# power-systems-v3.net
KiCad netlist of a schematic drawn in Altium Designer
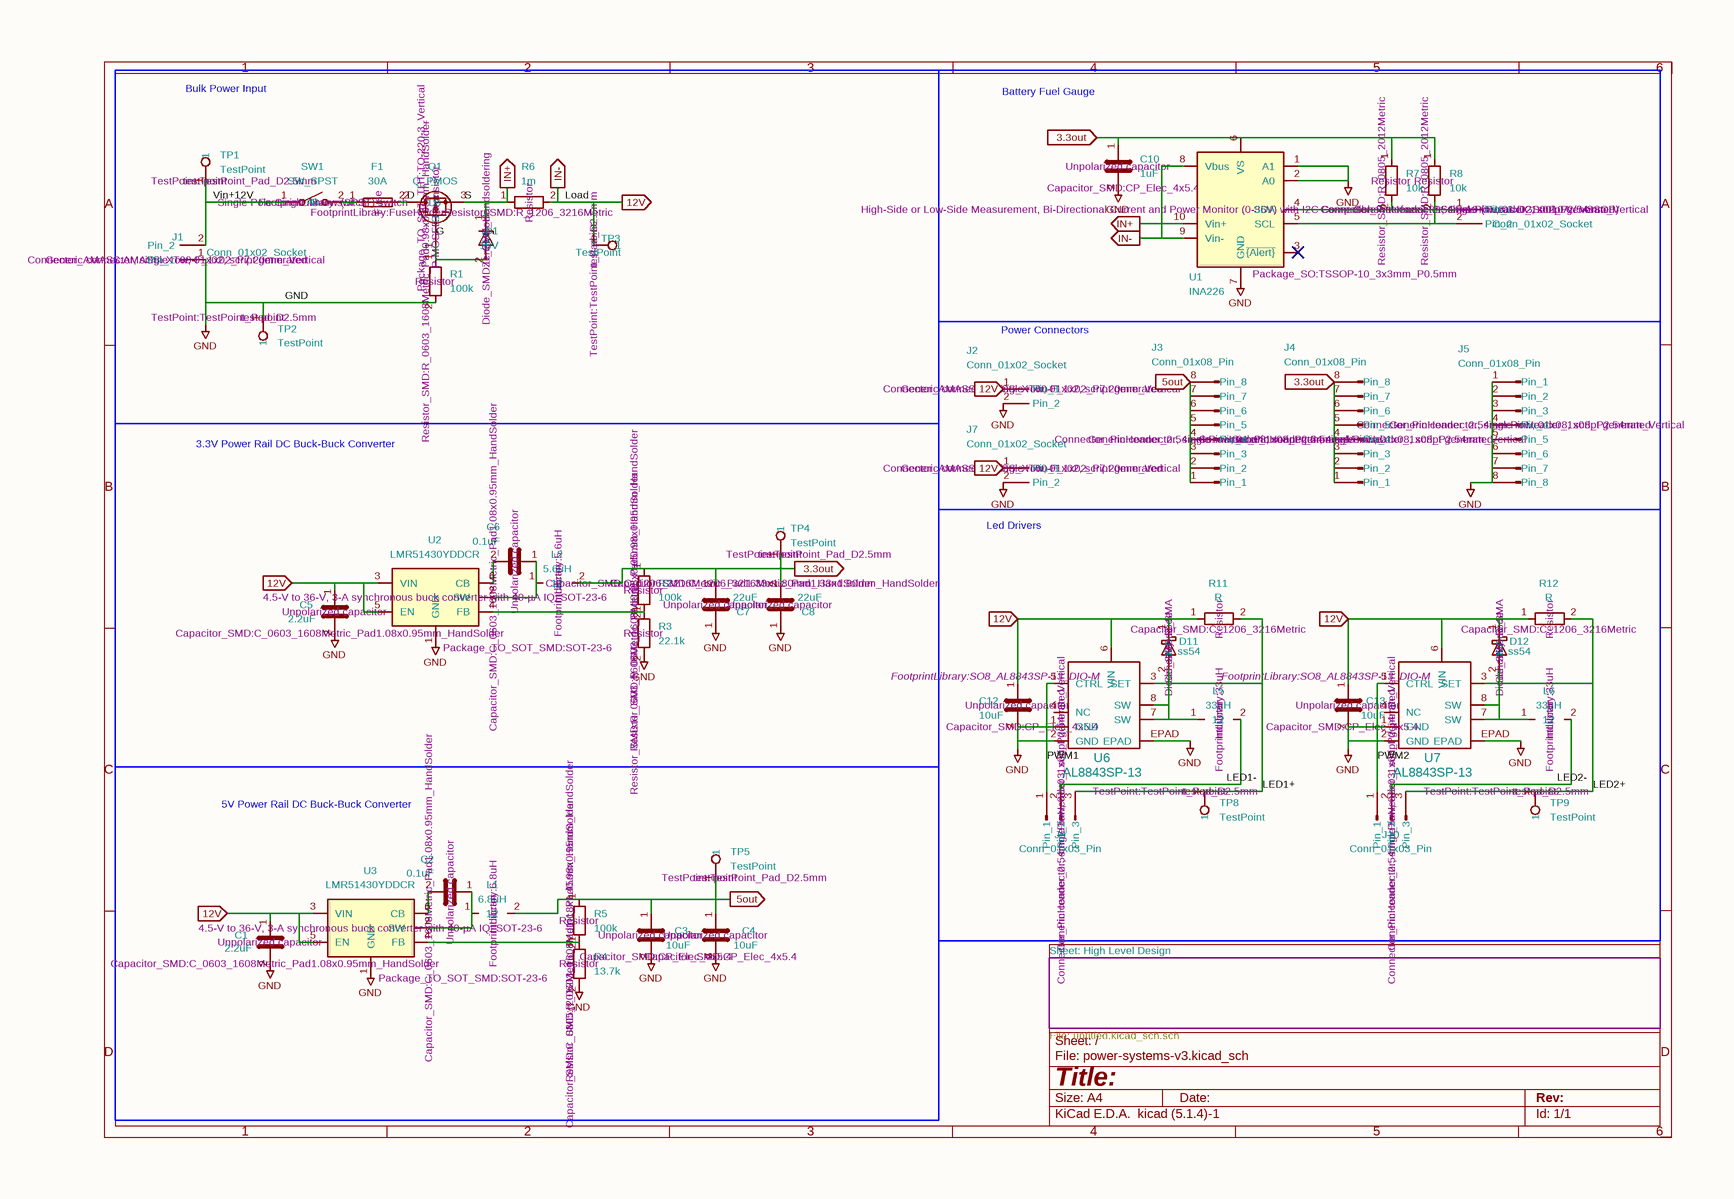
[diagram p0: power-systems-v3.SchDoc]

(export (version "E")
  (design (tool "Eeschema 10.0.6"))
  (components
    (comp (ref "C1")
      (value "2.2uF")
      (footprint "Capacitor_SMD:C_0603_1608Metric_Pad1.08x0.95mm_HandSolder")
      (description "Unpolarized capacitor")
      (libsource (lib "Device") (part "C"))
    )
    (comp (ref "C2")
      (value "0.1uF")
      (footprint "Capacitor_SMD:C_0603_1608Metric_Pad1.08x0.95mm_HandSolder")
      (description "Unpolarized capacitor")
      (libsource (lib "Device") (part "C"))
    )
    (comp (ref "C3")
      (value "10uF")
      (footprint "Capacitor_SMD:CP_Elec_4x5.4")
      (description "Unpolarized capacitor")
      (libsource (lib "Device") (part "C"))
    )
    (comp (ref "C4")
      (value "10uF")
      (footprint "Capacitor_SMD:CP_Elec_4x5.4")
      (description "Unpolarized capacitor")
      (libsource (lib "Device") (part "C"))
    )
    (comp (ref "C5")
      (value "2.2uF")
      (footprint "Capacitor_SMD:C_0603_1608Metric_Pad1.08x0.95mm_HandSolder")
      (description "Unpolarized capacitor")
      (libsource (lib "Device") (part "C"))
    )
    (comp (ref "C6")
      (value "0.1uF")
      (footprint "Capacitor_SMD:C_0603_1608Metric_Pad1.08x0.95mm_HandSolder")
      (description "Unpolarized capacitor")
      (libsource (lib "Device") (part "C"))
    )
    (comp (ref "C7")
      (value "22uF")
      (footprint "Capacitor_SMD:C_1206_3216Metric_Pad1.33x1.80mm_HandSolder")
      (description "Unpolarized capacitor")
      (libsource (lib "Device") (part "C"))
    )
    (comp (ref "C8")
      (value "22uF")
      (footprint "Capacitor_SMD:C_1206_3216Metric_Pad1.33x1.80mm_HandSolder")
      (description "Unpolarized capacitor")
      (libsource (lib "Device") (part "C"))
    )
    (comp (ref "C10")
      (value "1uF")
      (footprint "Capacitor_SMD:CP_Elec_4x5.4")
      (description "Unpolarized capacitor")
      (libsource (lib "Device") (part "C"))
    )
    (comp (ref "C12")
      (value "10uF")
      (footprint "Capacitor_SMD:CP_Elec_4x5.4")
      (description "Unpolarized capacitor")
      (libsource (lib "Device") (part "C"))
    )
    (comp (ref "C13")
      (value "10uF")
      (footprint "Capacitor_SMD:CP_Elec_4x5.4")
      (description "Unpolarized capacitor")
      (libsource (lib "Device") (part "C"))
    )
    (comp (ref "D1")
      (value "10V")
      (footprint "Diode_SMD:D_SMB_Handsoldering")
      (description "Zener diode")
      (libsource (lib "Device") (part "D_Zener"))
    )
    (comp (ref "D11")
      (value "ss54")
      (footprint "Diode_SMD:D_SMA")
      (description "Schottky diode")
      (libsource (lib "Device") (part "D_Schottky"))
    )
    (comp (ref "D12")
      (value "ss54")
      (footprint "Diode_SMD:D_SMA")
      (description "Schottky diode")
      (libsource (lib "Device") (part "D_Schottky"))
    )
    (comp (ref "F1")
      (value "30A")
      (footprint "FootprintLibrary:FuseHolder")
      (description "Fuse")
      (libsource (lib "Device") (part "Fuse"))
    )
    (comp (ref "J1")
      (value "Conn_01x02_Socket")
      (footprint "Connector_AMASS:AMASS_XT60-F_1x02_P7.20mm_Vertical")
      (description "Generic connector, single row, 01x02, script generated")
      (libsource (lib "Connector") (part "Conn_01x02_Socket"))
    )
    (comp (ref "J2")
      (value "Conn_01x02_Socket")
      (footprint "Connector_AMASS:AMASS_XT60-F_1x02_P7.20mm_Vertical")
      (description "Generic connector, single row, 01x02, script generated")
      (libsource (lib "Connector") (part "Conn_01x02_Socket"))
    )
    (comp (ref "J3")
      (value "Conn_01x08_Pin")
      (footprint "Connector_PinHeader_2.54mm:PinHeader_1x08_P2.54mm_Vertical")
      (description "Generic connector, single row, 01x08, script generated")
      (libsource (lib "") (part "Conn_01x08_Pin_1"))
    )
    (comp (ref "J4")
      (value "Conn_01x08_Pin")
      (footprint "Connector_PinHeader_2.54mm:PinHeader_1x08_P2.54mm_Vertical")
      (description "Generic connector, single row, 01x08, script generated")
      (libsource (lib "") (part "Conn_01x08_Pin_1"))
    )
    (comp (ref "J5")
      (value "Conn_01x08_Pin")
      (footprint "Connector_PinHeader_2.54mm:PinHeader_1x08_P2.54mm_Vertical")
      (description "Generic connector, single row, 01x08, script generated")
      (libsource (lib "Connector") (part "Conn_01x08_Pin"))
    )
    (comp (ref "J6")
      (value "Conn_01x02_Socket")
      (footprint "Connector_PinHeader_2.54mm:PinHeader_1x02_P2.54mm_Vertical")
      (description "Generic connector, single row, 01x02, script generated")
      (libsource (lib "Connector") (part "Conn_01x02_Socket"))
    )
    (comp (ref "J7")
      (value "Conn_01x02_Socket")
      (footprint "Connector_AMASS:AMASS_XT60-F_1x02_P7.20mm_Vertical")
      (description "Generic connector, single row, 01x02, script generated")
      (libsource (lib "Connector") (part "Conn_01x02_Socket"))
    )
    (comp (ref "J9")
      (value "Conn_01x03_Pin")
      (footprint "Connector_PinHeader_2.54mm:PinHeader_1x03_P2.54mm_Vertical")
      (description "Generic connector, single row, 01x03, script generated")
      (libsource (lib "Connector") (part "Conn_01x03_Pin"))
    )
    (comp (ref "J10")
      (value "Conn_01x03_Pin")
      (footprint "Connector_PinHeader_2.54mm:PinHeader_1x03_P2.54mm_Vertical")
      (description "Generic connector, single row, 01x03, script generated")
      (libsource (lib "Connector") (part "Conn_01x03_Pin"))
    )
    (comp (ref "L1")
      (value "6.8uH")
      (footprint "FootprintLibrary:6.8uH")
      (description "Inductor")
      (libsource (lib "Device") (part "L"))
    )
    (comp (ref "L2")
      (value "5.6uH")
      (footprint "FootprintLibrary:5.6uH")
      (description "Inductor")
      (libsource (lib "Device") (part "L"))
    )
    (comp (ref "L5")
      (value "33uH")
      (footprint "FootprintLibrary:33uH")
      (description "Inductor")
      (libsource (lib "Device") (part "L"))
    )
    (comp (ref "L6")
      (value "33uH")
      (footprint "FootprintLibrary:33uH")
      (description "Inductor")
      (libsource (lib "Device") (part "L"))
    )
    (comp (ref "Q1")
      (value "Q_PMOS")
      (footprint "Package_TO_SOT_THT:TO-220-3_Vertical")
      (description "P-MOSFET transistor")
      (libsource (lib "Device") (part "Q_PMOS"))
    )
    (comp (ref "R1")
      (value "100k")
      (footprint "Resistor_SMD:R_0603_1608Metric_Pad0.98x0.95mm_HandSolder")
      (description "Resistor")
      (libsource (lib "") (part "R_1"))
    )
    (comp (ref "R2")
      (value "100k")
      (footprint "Resistor_SMD:R_0603_1608Metric_Pad0.98x0.95mm_HandSolder")
      (description "Resistor")
      (libsource (lib "") (part "R_1"))
    )
    (comp (ref "R3")
      (value "22.1k")
      (footprint "Resistor_SMD:R_0603_1608Metric_Pad0.98x0.95mm_HandSolder")
      (description "Resistor")
      (libsource (lib "") (part "R_1"))
    )
    (comp (ref "R4")
      (value "13.7k")
      (footprint "Capacitor_SMD:C_0805_2012Metric_Pad1.18x1.45mm_HandSolder")
      (description "Resistor")
      (libsource (lib "") (part "R_1"))
    )
    (comp (ref "R5")
      (value "100k")
      (footprint "Resistor_SMD:R_0603_1608Metric_Pad0.98x0.95mm_HandSolder")
      (description "Resistor")
      (libsource (lib "") (part "R_1"))
    )
    (comp (ref "R6")
      (value "1m")
      (footprint "Resistor_SMD:R_1206_3216Metric")
      (description "Resistor")
      (libsource (lib "Device") (part "R"))
    )
    (comp (ref "R7")
      (value "10k")
      (footprint "Resistor_SMD:R_0805_2012Metric")
      (description "Resistor")
      (libsource (lib "") (part "R_1"))
    )
    (comp (ref "R8")
      (value "10k")
      (footprint "Resistor_SMD:R_0805_2012Metric")
      (description "Resistor")
      (libsource (lib "") (part "R_1"))
    )
    (comp (ref "R11")
      (value "R")
      (footprint "Capacitor_SMD:C_1206_3216Metric")
      (description "Resistor")
      (libsource (lib "Device") (part "R"))
    )
    (comp (ref "R12")
      (value "R")
      (footprint "Capacitor_SMD:C_1206_3216Metric")
      (description "Resistor")
      (libsource (lib "Device") (part "R"))
    )
    (comp (ref "SW1")
      (value "SW_SPST")
      (footprint "FootprintLibrary:switch")
      (description "Single Pole Single Throw (SPST) switch")
      (libsource (lib "Switch") (part "SW_SPST"))
    )
    (comp (ref "TP1")
      (value "TestPoint")
      (footprint "TestPoint:TestPoint_Pad_D2.5mm")
      (description "test point")
      (libsource (lib "Connector") (part "TestPoint"))
    )
    (comp (ref "TP2")
      (value "TestPoint")
      (footprint "TestPoint:TestPoint_Pad_D2.5mm")
      (description "test point")
      (libsource (lib "Connector") (part "TestPoint"))
    )
    (comp (ref "TP3")
      (value "TestPoint")
      (footprint "TestPoint:TestPoint_Pad_D2.5mm")
      (description "test point")
      (libsource (lib "Connector") (part "TestPoint"))
    )
    (comp (ref "TP4")
      (value "TestPoint")
      (footprint "TestPoint:TestPoint_Pad_D2.5mm")
      (description "test point")
      (libsource (lib "Connector") (part "TestPoint"))
    )
    (comp (ref "TP5")
      (value "TestPoint")
      (footprint "TestPoint:TestPoint_Pad_D2.5mm")
      (description "test point")
      (libsource (lib "Connector") (part "TestPoint"))
    )
    (comp (ref "TP8")
      (value "TestPoint")
      (footprint "TestPoint:TestPoint_Pad_D2.5mm")
      (description "test point")
      (libsource (lib "Connector") (part "TestPoint"))
    )
    (comp (ref "TP9")
      (value "TestPoint")
      (footprint "TestPoint:TestPoint_Pad_D2.5mm")
      (description "test point")
      (libsource (lib "Connector") (part "TestPoint"))
    )
    (comp (ref "U1")
      (value "INA226")
      (footprint "Package_SO:TSSOP-10_3x3mm_P0.5mm")
      (description "High-Side or Low-Side Measurement, Bi-Directional Current and Power Monitor (0-36V) with I2C Compatible Interface, TSSOP-10 (Texas DGS0010A / VSSOP)")
      (libsource (lib "Sensor_Energy") (part "INA226"))
    )
    (comp (ref "U2")
      (value "LMR51430YDDCR")
      (footprint "Package_TO_SOT_SMD:SOT-23-6")
      (description "4.5-V to 36-V, 3-A synchronous buck converter with 40-µA IQ, SOT-23-6")
      (libsource (lib "Regulator_Switching") (part "LMR51430"))
    )
    (comp (ref "U3")
      (value "LMR51430YDDCR")
      (footprint "Package_TO_SOT_SMD:SOT-23-6")
      (description "4.5-V to 36-V, 3-A synchronous buck converter with 40-µA IQ, SOT-23-6")
      (libsource (lib "Regulator_Switching") (part "LMR51430"))
    )
    (comp (ref "U6")
      (value "AL8843SP-13")
      (footprint "FootprintLibrary:SO8_AL8843SP-13_DIO-M")
      (libsource (lib "*") (part "AL8843SP-13_1"))
    )
    (comp (ref "U7")
      (value "AL8843SP-13")
      (footprint "FootprintLibrary:SO8_AL8843SP-13_DIO-M")
      (libsource (lib "*") (part "AL8843SP-13_1"))
    )
  )
  (nets
    (net (code "1") (name "/3.3out") (class "Default")
      (node (ref "C10") (pin "1") (pinfunction "1_1") (pintype "passive"))
      (node (ref "C7") (pin "2") (pinfunction "2_2") (pintype "passive"))
      (node (ref "C8") (pin "2") (pinfunction "2_2") (pintype "passive"))
      (node (ref "J4") (pin "1") (pinfunction "Pin_1_1") (pintype "passive"))
      (node (ref "J4") (pin "2") (pinfunction "Pin_2_2") (pintype "passive"))
      (node (ref "J4") (pin "3") (pinfunction "Pin_3_3") (pintype "passive"))
      (node (ref "J4") (pin "4") (pinfunction "Pin_4_4") (pintype "passive"))
      (node (ref "J4") (pin "5") (pinfunction "Pin_5_5") (pintype "passive"))
      (node (ref "J4") (pin "6") (pinfunction "Pin_6_6") (pintype "passive"))
      (node (ref "J4") (pin "7") (pinfunction "Pin_7_7") (pintype "passive"))
      (node (ref "J4") (pin "8") (pinfunction "Pin_8_8") (pintype "passive"))
      (node (ref "L2") (pin "2") (pinfunction "2_2") (pintype "passive"))
      (node (ref "R2") (pin "1") (pinfunction "1_1") (pintype "passive"))
      (node (ref "R7") (pin "1") (pinfunction "1_1") (pintype "passive"))
      (node (ref "R8") (pin "1") (pinfunction "1_1") (pintype "passive"))
      (node (ref "TP4") (pin "1") (pinfunction "1_1") (pintype "passive"))
      (node (ref "U1") (pin "6") (pinfunction "VS_6") (pintype "passive"))
    )
    (net (code "2") (name "/5out") (class "Default")
      (node (ref "C3") (pin "1") (pinfunction "1_1") (pintype "passive"))
      (node (ref "C4") (pin "1") (pinfunction "1_1") (pintype "passive"))
      (node (ref "J3") (pin "1") (pinfunction "Pin_1_1") (pintype "passive"))
      (node (ref "J3") (pin "2") (pinfunction "Pin_2_2") (pintype "passive"))
      (node (ref "J3") (pin "3") (pinfunction "Pin_3_3") (pintype "passive"))
      (node (ref "J3") (pin "4") (pinfunction "Pin_4_4") (pintype "passive"))
      (node (ref "J3") (pin "5") (pinfunction "Pin_5_5") (pintype "passive"))
      (node (ref "J3") (pin "6") (pinfunction "Pin_6_6") (pintype "passive"))
      (node (ref "J3") (pin "7") (pinfunction "Pin_7_7") (pintype "passive"))
      (node (ref "J3") (pin "8") (pinfunction "Pin_8_8") (pintype "passive"))
      (node (ref "L1") (pin "2") (pinfunction "2_2") (pintype "passive"))
      (node (ref "R5") (pin "1") (pinfunction "1_1") (pintype "passive"))
      (node (ref "TP5") (pin "1") (pinfunction "1_1") (pintype "passive"))
    )
    (net (code "3") (name "/D") (class "Default")
      (node (ref "F1") (pin "2") (pinfunction "2_2") (pintype "passive"))
      (node (ref "Q1") (pin "2") (pinfunction "D_2") (pintype "passive"))
    )
    (net (code "5") (name "/LED1+") (class "Default")
      (node (ref "J9") (pin "3") (pinfunction "Pin_3_3") (pintype "passive"))
      (node (ref "R11") (pin "2") (pinfunction "2_2") (pintype "passive"))
      (node (ref "TP8") (pin "1") (pinfunction "1_1") (pintype "passive"))
      (node (ref "U6") (pin "3") (pinfunction "SET_3") (pintype "passive"))
    )
    (net (code "6") (name "/LED1-") (class "Default")
      (node (ref "J9") (pin "2") (pinfunction "Pin_2_2") (pintype "passive"))
      (node (ref "L5") (pin "2") (pinfunction "2_2") (pintype "passive"))
    )
    (net (code "7") (name "/LED2+") (class "Default")
      (node (ref "J10") (pin "3") (pinfunction "Pin_3_3") (pintype "passive"))
      (node (ref "R12") (pin "2") (pinfunction "2_2") (pintype "passive"))
      (node (ref "TP9") (pin "1") (pinfunction "1_1") (pintype "passive"))
      (node (ref "U7") (pin "3") (pinfunction "SET_3") (pintype "passive"))
    )
    (net (code "8") (name "/LED2-") (class "Default")
      (node (ref "J10") (pin "2") (pinfunction "Pin_2_2") (pintype "passive"))
      (node (ref "L6") (pin "2") (pinfunction "2_2") (pintype "passive"))
    )
    (net (code "9") (name "/Load") (class "Default")
      (node (ref "C1") (pin "1") (pinfunction "1_1") (pintype "passive"))
      (node (ref "C12") (pin "1") (pinfunction "1_1") (pintype "passive"))
      (node (ref "C13") (pin "1") (pinfunction "1_1") (pintype "passive"))
      (node (ref "C5") (pin "1") (pinfunction "1_1") (pintype "passive"))
      (node (ref "D11") (pin "1") (pinfunction "K_1") (pintype "passive"))
      (node (ref "D12") (pin "1") (pinfunction "K_1") (pintype "passive"))
      (node (ref "J2") (pin "1") (pinfunction "Pin_1_1") (pintype "passive"))
      (node (ref "J7") (pin "1") (pinfunction "Pin_1_1") (pintype "passive"))
      (node (ref "R11") (pin "1") (pinfunction "1_1") (pintype "passive"))
      (node (ref "R12") (pin "1") (pinfunction "1_1") (pintype "passive"))
      (node (ref "R6") (pin "2") (pinfunction "2_2") (pintype "passive"))
      (node (ref "TP3") (pin "1") (pinfunction "1_1") (pintype "passive"))
      (node (ref "U1") (pin "8") (pinfunction "Vbus_8") (pintype "passive"))
      (node (ref "U1") (pin "9") (pinfunction "Vin-_9") (pintype "passive"))
      (node (ref "U2") (pin "3") (pinfunction "VIN_3") (pintype "passive"))
      (node (ref "U2") (pin "5") (pinfunction "EN_5") (pintype "passive"))
      (node (ref "U3") (pin "3") (pinfunction "VIN_3") (pintype "passive"))
      (node (ref "U3") (pin "5") (pinfunction "EN_5") (pintype "passive"))
      (node (ref "U6") (pin "6") (pinfunction "VIN_6") (pintype "passive"))
      (node (ref "U7") (pin "6") (pinfunction "VIN_6") (pintype "passive"))
    )
    (net (code "10") (name "/PWM1") (class "Default")
      (node (ref "J9") (pin "1") (pinfunction "Pin_1_1") (pintype "passive"))
      (node (ref "U6") (pin "5") (pinfunction "CTRL_5") (pintype "passive"))
    )
    (net (code "11") (name "/PWM2") (class "Default")
      (node (ref "J10") (pin "1") (pinfunction "Pin_1_1") (pintype "passive"))
      (node (ref "U7") (pin "5") (pinfunction "CTRL_5") (pintype "passive"))
    )
    (net (code "12") (name "/S") (class "Default")
      (node (ref "D1") (pin "1") (pinfunction "K_1") (pintype "passive"))
      (node (ref "Q1") (pin "3") (pinfunction "S_3") (pintype "passive"))
      (node (ref "R6") (pin "1") (pinfunction "1_1") (pintype "passive"))
      (node (ref "U1") (pin "10") (pinfunction "Vin+_10") (pintype "passive"))
    )
    (net (code "13") (name "/Vin+12V") (class "Default")
      (node (ref "J1") (pin "2") (pinfunction "Pin_2_2") (pintype "passive"))
      (node (ref "SW1") (pin "1") (pinfunction "A_1") (pintype "passive"))
      (node (ref "TP1") (pin "1") (pinfunction "1_1") (pintype "passive"))
    )
    (net (code "14") (name "GND") (class "Default")
      (node (ref "C1") (pin "2") (pinfunction "2_2") (pintype "passive"))
      (node (ref "C10") (pin "2") (pinfunction "2_2") (pintype "passive"))
      (node (ref "C12") (pin "2") (pinfunction "2_2") (pintype "passive"))
      (node (ref "C13") (pin "2") (pinfunction "2_2") (pintype "passive"))
      (node (ref "C3") (pin "2") (pinfunction "2_2") (pintype "passive"))
      (node (ref "C4") (pin "2") (pinfunction "2_2") (pintype "passive"))
      (node (ref "C5") (pin "2") (pinfunction "2_2") (pintype "passive"))
      (node (ref "C7") (pin "1") (pinfunction "1_1") (pintype "passive"))
      (node (ref "C8") (pin "1") (pinfunction "1_1") (pintype "passive"))
      (node (ref "J1") (pin "1") (pinfunction "Pin_1_1") (pintype "passive"))
      (node (ref "J2") (pin "2") (pinfunction "Pin_2_2") (pintype "passive"))
      (node (ref "J5") (pin "1") (pinfunction "Pin_1_1") (pintype "passive"))
      (node (ref "J5") (pin "2") (pinfunction "Pin_2_2") (pintype "passive"))
      (node (ref "J5") (pin "3") (pinfunction "Pin_3_3") (pintype "passive"))
      (node (ref "J5") (pin "4") (pinfunction "Pin_4_4") (pintype "passive"))
      (node (ref "J5") (pin "5") (pinfunction "Pin_5_5") (pintype "passive"))
      (node (ref "J5") (pin "6") (pinfunction "Pin_6_6") (pintype "passive"))
      (node (ref "J5") (pin "7") (pinfunction "Pin_7_7") (pintype "passive"))
      (node (ref "J5") (pin "8") (pinfunction "Pin_8_8") (pintype "passive"))
      (node (ref "J7") (pin "2") (pinfunction "Pin_2_2") (pintype "passive"))
      (node (ref "R1") (pin "2") (pinfunction "2_2") (pintype "passive"))
      (node (ref "R3") (pin "2") (pinfunction "2_2") (pintype "passive"))
      (node (ref "R4") (pin "2") (pinfunction "2_2") (pintype "passive"))
      (node (ref "TP2") (pin "1") (pinfunction "1_1") (pintype "passive"))
      (node (ref "U1") (pin "1") (pinfunction "A1_1") (pintype "passive"))
      (node (ref "U1") (pin "2") (pinfunction "A0_2") (pintype "passive"))
      (node (ref "U1") (pin "7") (pinfunction "GND_7") (pintype "passive"))
      (node (ref "U2") (pin "1") (pinfunction "GND_1") (pintype "passive"))
      (node (ref "U3") (pin "1") (pinfunction "GND_1") (pintype "passive"))
      (node (ref "U6") (pin "1") (pinfunction "GND_1") (pintype "passive"))
      (node (ref "U6") (pin "2") (pinfunction "GND_2") (pintype "passive"))
      (node (ref "U6") (pin "EPAD") (pinfunction "EPAD_EPAD") (pintype "passive"))
      (node (ref "U7") (pin "1") (pinfunction "GND_1") (pintype "passive"))
      (node (ref "U7") (pin "2") (pinfunction "GND_2") (pintype "passive"))
      (node (ref "U7") (pin "EPAD") (pinfunction "EPAD_EPAD") (pintype "passive"))
    )
    (net (code "15") (name "Net-(D1-A)") (class "Default")
      (node (ref "D1") (pin "2") (pinfunction "A_2") (pintype "passive"))
      (node (ref "Q1") (pin "1") (pinfunction "G_1") (pintype "passive"))
      (node (ref "R1") (pin "1") (pinfunction "1_1") (pintype "passive"))
    )
    (net (code "16") (name "Net-(D11-A)") (class "Default")
      (node (ref "D11") (pin "2") (pinfunction "A_2") (pintype "passive"))
      (node (ref "L5") (pin "1") (pinfunction "1_1") (pintype "passive"))
      (node (ref "U6") (pin "7") (pinfunction "SW_7") (pintype "passive"))
      (node (ref "U6") (pin "8") (pinfunction "SW_8") (pintype "passive"))
    )
    (net (code "17") (name "Net-(D12-A)") (class "Default")
      (node (ref "D12") (pin "2") (pinfunction "A_2") (pintype "passive"))
      (node (ref "L6") (pin "1") (pinfunction "1_1") (pintype "passive"))
      (node (ref "U7") (pin "7") (pinfunction "SW_7") (pintype "passive"))
      (node (ref "U7") (pin "8") (pinfunction "SW_8") (pintype "passive"))
    )
    (net (code "18") (name "Net-(J6-Pin_1)") (class "Default")
      (node (ref "J6") (pin "1") (pinfunction "Pin_1_1") (pintype "passive"))
      (node (ref "R7") (pin "2") (pinfunction "2_2") (pintype "passive"))
      (node (ref "U1") (pin "4") (pinfunction "SDA_4") (pintype "passive"))
    )
    (net (code "19") (name "Net-(J6-Pin_2)") (class "Default")
      (node (ref "J6") (pin "2") (pinfunction "Pin_2_2") (pintype "passive"))
      (node (ref "R8") (pin "2") (pinfunction "2_2") (pintype "passive"))
      (node (ref "U1") (pin "5") (pinfunction "SCL_5") (pintype "passive"))
    )
    (net (code "20") (name "Net-(SW1-B)") (class "Default")
      (node (ref "F1") (pin "1") (pinfunction "1_1") (pintype "passive"))
      (node (ref "SW1") (pin "2") (pinfunction "B_2") (pintype "passive"))
    )
    (net (code "21") (name "Net-(U2-CB)") (class "Default")
      (node (ref "C6") (pin "2") (pinfunction "2_2") (pintype "passive"))
      (node (ref "U2") (pin "6") (pinfunction "CB_6") (pintype "passive"))
    )
    (net (code "22") (name "Net-(U2-FB)") (class "Default")
      (node (ref "R2") (pin "2") (pinfunction "2_2") (pintype "passive"))
      (node (ref "R3") (pin "1") (pinfunction "1_1") (pintype "passive"))
      (node (ref "U2") (pin "4") (pinfunction "FB_4") (pintype "passive"))
    )
    (net (code "23") (name "Net-(U2-SW)") (class "Default")
      (node (ref "C6") (pin "1") (pinfunction "1_1") (pintype "passive"))
      (node (ref "L2") (pin "1") (pinfunction "1_1") (pintype "passive"))
      (node (ref "U2") (pin "2") (pinfunction "SW_2") (pintype "passive"))
    )
    (net (code "24") (name "Net-(U3-CB)") (class "Default")
      (node (ref "C2") (pin "2") (pinfunction "2_2") (pintype "passive"))
      (node (ref "U3") (pin "6") (pinfunction "CB_6") (pintype "passive"))
    )
    (net (code "25") (name "Net-(U3-FB)") (class "Default")
      (node (ref "R4") (pin "1") (pinfunction "1_1") (pintype "passive"))
      (node (ref "R5") (pin "2") (pinfunction "2_2") (pintype "passive"))
      (node (ref "U3") (pin "4") (pinfunction "FB_4") (pintype "passive"))
    )
    (net (code "26") (name "Net-(U3-SW)") (class "Default")
      (node (ref "C2") (pin "1") (pinfunction "1_1") (pintype "passive"))
      (node (ref "L1") (pin "1") (pinfunction "1_1") (pintype "passive"))
      (node (ref "U3") (pin "2") (pinfunction "SW_2") (pintype "passive"))
    )
    (net (code "27") (name "unconnected-(U1-~{{Alert}}-Pad3)") (class "Default")
      (node (ref "U1") (pin "3") (pinfunction "~{{Alert}}_3") (pintype "passive+no_connect"))
    )
    (net (code "28") (name "unconnected-(U6-NC-Pad4)") (class "Default")
      (node (ref "U6") (pin "4") (pinfunction "NC_4") (pintype "passive"))
    )
    (net (code "29") (name "unconnected-(U7-NC-Pad4)") (class "Default")
      (node (ref "U7") (pin "4") (pinfunction "NC_4") (pintype "passive"))
    )
  )
)
